# USB.net
KiCad netlist of a schematic drawn in Altium Designer
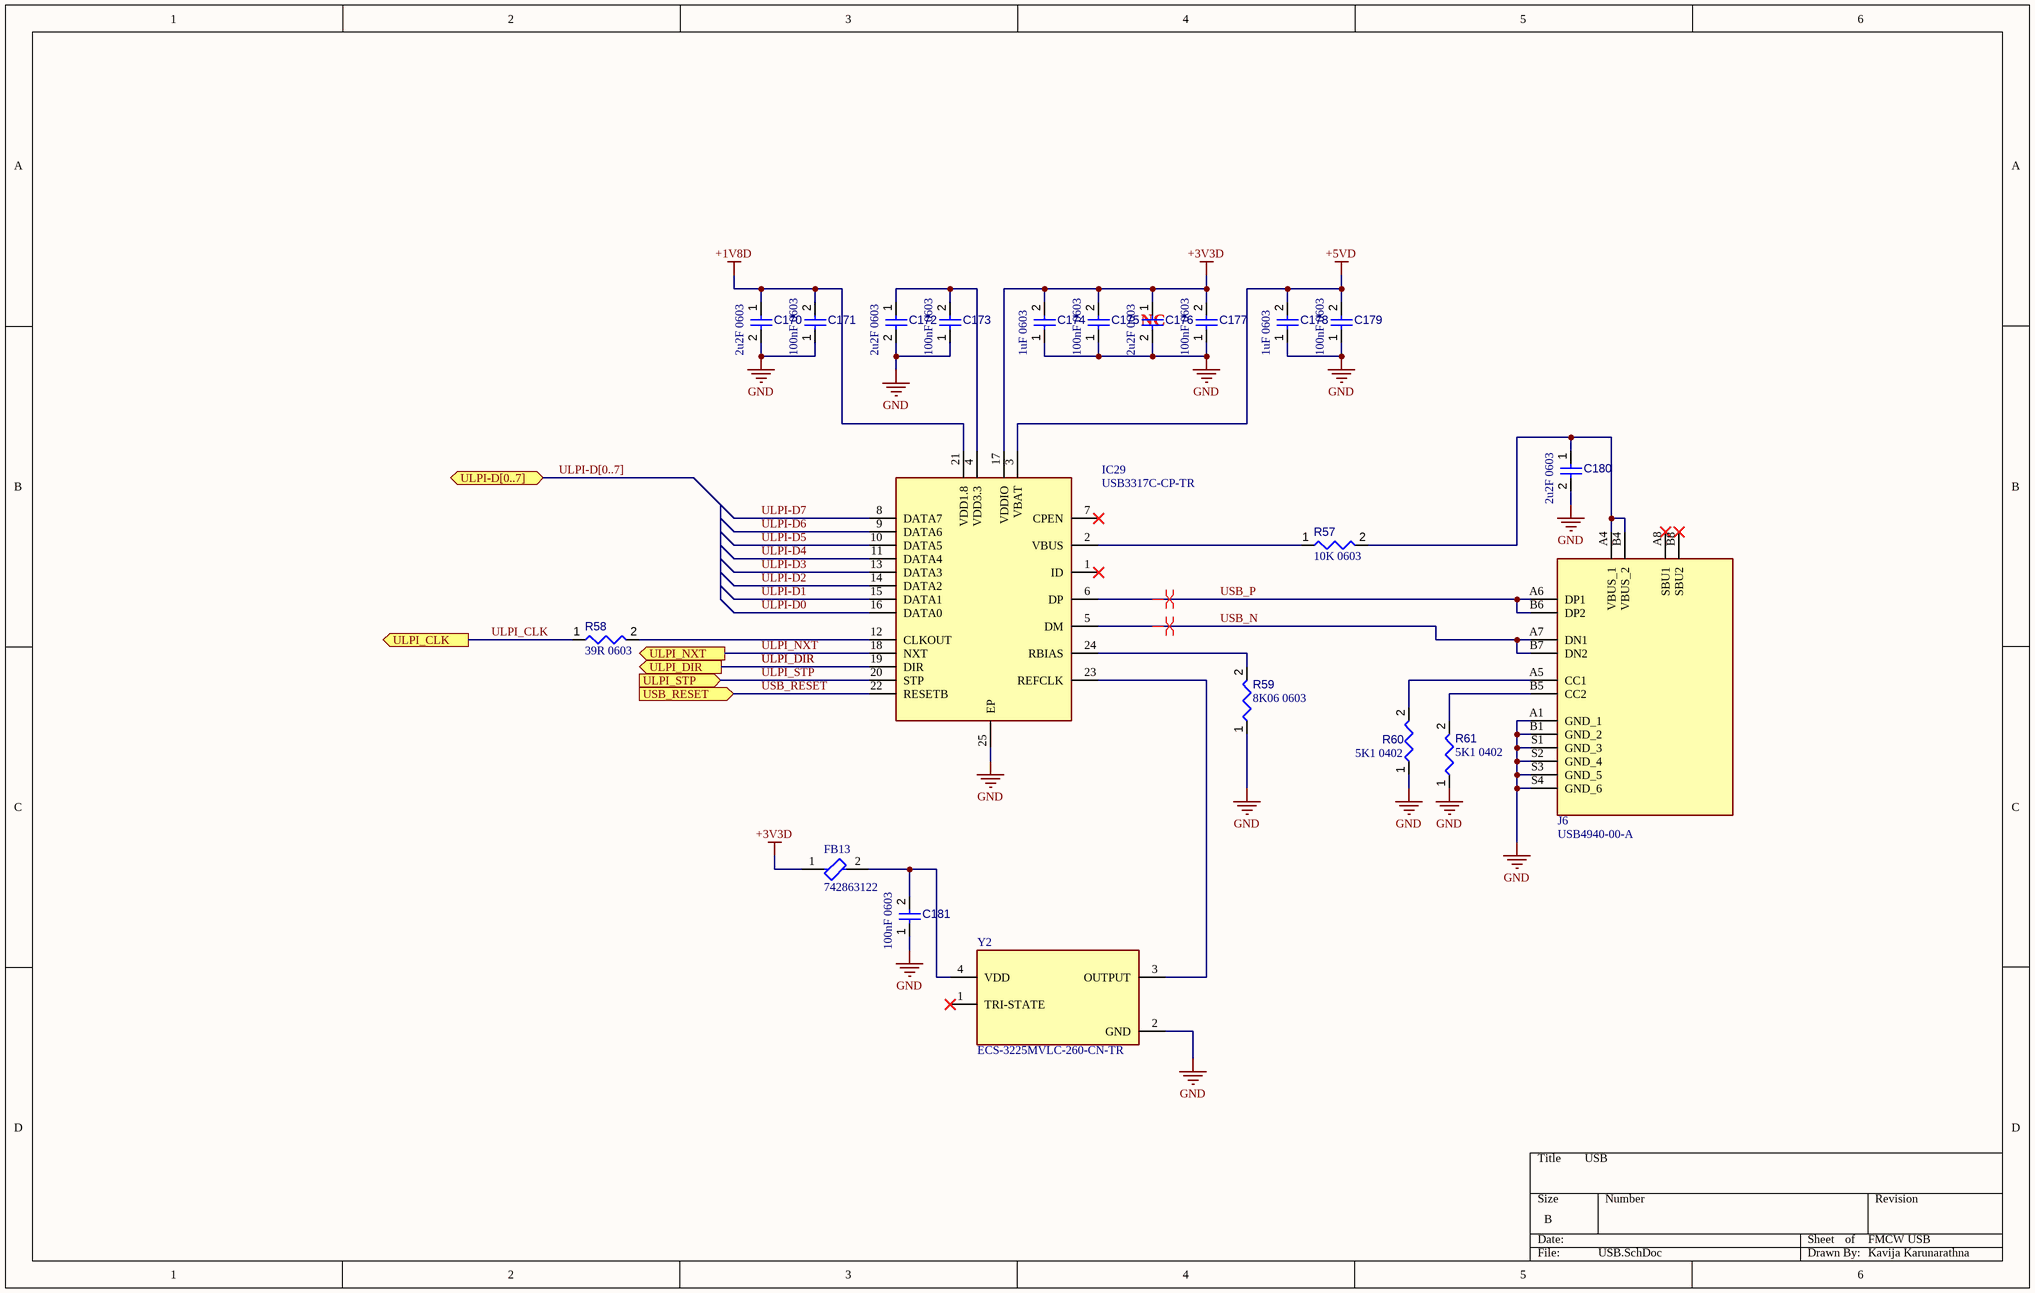
[diagram p0: USB.SchDoc]

(export (version "E")
  (design (tool "Eeschema 10.0.6"))
  (components
    (comp (ref "C170")
      (value "2u2F 0603")
      (footprint "CAPC0603(1608)100_L")
      (description "Multilayer Ceramic Capacitors MLCC - SMD/SMT 0603 10nF 16volts X7R 10%")
      (fields (field (name "TOLERANCE") "20%") (field (name "MANUFACTURER PART NO") "VJ0603G225KXQCW1BC"))
      (libsource (lib "Kavija Karunarathna") (part "CAP-NP-2"))
    )
    (comp (ref "C171")
      (value "100nF 0603")
      (footprint "CAPC0603(1608)100_L")
      (description "Chip Capacitor, 1µF +/-0.1%, 25V, 0603, Thickness 1 mm")
      (fields (field (name "TOLERANCE") "20%") (field (name "MANUFACTURER PART NO") "0603X104K250CT"))
      (libsource (lib "Kavija Karunarathna") (part "CAP-NP-2"))
    )
    (comp (ref "C172")
      (value "2u2F 0603")
      (footprint "CAPC0603(1608)100_L")
      (description "Multilayer Ceramic Capacitors MLCC - SMD/SMT 0603 10nF 16volts X7R 10%")
      (fields (field (name "TOLERANCE") "20%") (field (name "MANUFACTURER PART NO") "VJ0603G225KXQCW1BC"))
      (libsource (lib "Kavija Karunarathna") (part "CAP-NP-2"))
    )
    (comp (ref "C173")
      (value "100nF 0603")
      (footprint "CAPC0603(1608)100_L")
      (description "Chip Capacitor, 1µF +/-0.1%, 25V, 0603, Thickness 1 mm")
      (fields (field (name "TOLERANCE") "20%") (field (name "MANUFACTURER PART NO") "0603X104K250CT"))
      (libsource (lib "Kavija Karunarathna") (part "CAP-NP-2"))
    )
    (comp (ref "C174")
      (value "1uF 0603")
      (footprint "CAPC0603(1608)100_L")
      (description "Chip Capacitor, 1µF +/-0.1%, 25V, 0603, Thickness 1 mm")
      (fields (field (name "TOLERANCE") "20%") (field (name "MANUFACTURER PART NO") "0603YC105KAZ2A"))
      (libsource (lib "Kavija Karunarathna") (part "CAP-NP-2"))
    )
    (comp (ref "C175")
      (value "100nF 0603")
      (footprint "CAPC0603(1608)100_L")
      (description "Chip Capacitor, 1µF +/-0.1%, 25V, 0603, Thickness 1 mm")
      (fields (field (name "TOLERANCE") "20%") (field (name "MANUFACTURER PART NO") "0603X104K250CT"))
      (libsource (lib "Kavija Karunarathna") (part "CAP-NP-2"))
    )
    (comp (ref "C176")
      (value "2u2F 0603")
      (footprint "CAPC0603(1608)100_L")
      (description "Multilayer Ceramic Capacitors MLCC - SMD/SMT 0603 10nF 16volts X7R 10%")
      (fields (field (name "TOLERANCE") "20%") (field (name "MANUFACTURER PART NO") "VJ0603G225KXQCW1BC"))
      (libsource (lib "Kavija Karunarathna") (part "CAP-NP-2"))
    )
    (comp (ref "C177")
      (value "100nF 0603")
      (footprint "CAPC0603(1608)100_L")
      (description "Chip Capacitor, 1µF +/-0.1%, 25V, 0603, Thickness 1 mm")
      (fields (field (name "TOLERANCE") "20%") (field (name "MANUFACTURER PART NO") "0603X104K250CT"))
      (libsource (lib "Kavija Karunarathna") (part "CAP-NP-2"))
    )
    (comp (ref "C178")
      (value "1uF 0603")
      (footprint "CAPC0603(1608)100_L")
      (description "Chip Capacitor, 1µF +/-0.1%, 25V, 0603, Thickness 1 mm")
      (fields (field (name "TOLERANCE") "20%") (field (name "MANUFACTURER PART NO") "0603YC105KAZ2A"))
      (libsource (lib "Kavija Karunarathna") (part "CAP-NP-2"))
    )
    (comp (ref "C179")
      (value "100nF 0603")
      (footprint "CAPC0603(1608)100_L")
      (description "Chip Capacitor, 1µF +/-0.1%, 25V, 0603, Thickness 1 mm")
      (fields (field (name "TOLERANCE") "20%") (field (name "MANUFACTURER PART NO") "0603X104K250CT"))
      (libsource (lib "Kavija Karunarathna") (part "CAP-NP-2"))
    )
    (comp (ref "C180")
      (value "2u2F 0603")
      (footprint "CAPC0603(1608)100_L")
      (description "Multilayer Ceramic Capacitors MLCC - SMD/SMT 0603 10nF 16volts X7R 10%")
      (fields (field (name "TOLERANCE") "20%") (field (name "MANUFACTURER PART NO") "VJ0603G225KXQCW1BC"))
      (libsource (lib "Kavija Karunarathna") (part "CAP-NP-2"))
    )
    (comp (ref "C181")
      (value "100nF 0603")
      (footprint "CAPC0603(1608)100_L")
      (description "Chip Capacitor, 1µF +/-0.1%, 25V, 0603, Thickness 1 mm")
      (fields (field (name "TOLERANCE") "20%") (field (name "MANUFACTURER PART NO") "0603X104K250CT"))
      (libsource (lib "Kavija Karunarathna") (part "CAP-NP-2"))
    )
    (comp (ref "FB13")
      (value "742863122")
      (footprint "FB-0603")
      (description "FERRITE BEAD 0603")
      (fields (field (name "MOUSER PART NO") "710-742863122"))
      (libsource (lib "SchLib") (part "742792662-FB"))
    )
    (comp (ref "IC29")
      (value "USB3317C-CP-TR")
      (footprint "QFN50P400X400X100-25N-D")
      (description "Integrated Circuit")
      (fields (field (name "MOUSER PART NO") "886-USB3317C-CP-TR"))
      (libsource (lib "SchLib") (part "USB3317C-CP-TR"))
    )
    (comp (ref "J6")
      (value "USB4940-00-A")
      (footprint "USB494000A")
      (description "USB Connectors USB Type C, 2.0, 16P, Receptacle, Horizontal, Top Mount, SMT,T&R")
      (fields (field (name "MOUSER PART NO") "640-USB4940-00-A"))
      (libsource (lib "SchLib") (part "USB4940-00-A"))
    )
    (comp (ref "R57")
      (value "10K 0603")
      (footprint "RESC0603(1608)_L")
      (description "Thin Film Resistors - SMD CHIP RESISTOR Precision")
      (fields (field (name "POWER") "100mW") (field (name "TOLERANCE") "5%"))
      (libsource (lib "Kavija Karunarathna") (part "120R3J"))
    )
    (comp (ref "R58")
      (value "39R 0603")
      (footprint "RESC0603(1608)_L")
      (description "Thick Film Resistors - SMD 1/10Watt 39ohms 1% Commercial Use")
      (fields (field (name "POWER") "100mW") (field (name "TOLERANCE") "5%"))
      (libsource (lib "Kavija Karunarathna") (part "120R3J"))
    )
    (comp (ref "R59")
      (value "8K06 0603")
      (footprint "RESC0603(1608)_L")
      (description "Thin Film Resistors - SMD RN 0603 8K06 0.1% 10PPM")
      (fields (field (name "POWER") "100mW") (field (name "TOLERANCE") "5%"))
      (libsource (lib "Kavija Karunarathna") (part "120R3J"))
    )
    (comp (ref "R60")
      (value "5K1 0402")
      (footprint "RESC0402(1005)_L")
      (description "Thick Film Resistors - SMD 1/10 Watt 5.1Kohms 1%")
      (fields (field (name "TOLERANCE") "1%") (field (name "POWER") "100mW"))
      (libsource (lib "Kavija Karunarathna") (part "383KR2F"))
    )
    (comp (ref "R61")
      (value "5K1 0402")
      (footprint "RESC0402(1005)_L")
      (description "Thick Film Resistors - SMD 1/10 Watt 5.1Kohms 1%")
      (fields (field (name "TOLERANCE") "1%") (field (name "POWER") "100mW"))
      (libsource (lib "Kavija Karunarathna") (part "383KR2F"))
    )
    (comp (ref "Y2")
      (value "ECS-3225MVLC-260-CN-TR")
      (footprint "OSC_ECS-3225MVLC-260-CN-TR")
      (description "26 MHz XO (Standard) CMOS Oscillator 1.8V ~ 3.3V Enable/Disable 4-SMD, No Lead")
      (fields (field (name "MF") "ECS Inc."))
      (libsource (lib "Kavija Karunarathna") (part "ECS-3225MVLC-260-CN-TR"))
    )
  )
  (nets
    (net (code "1") (name "+1V8D") (class "Default")
      (node (ref "C170") (pin "1") (pinfunction "1_1") (pintype "passive"))
      (node (ref "C171") (pin "2") (pinfunction "2_2") (pintype "passive"))
      (node (ref "IC29") (pin "21") (pinfunction "VDD1.8_21") (pintype "passive"))
    )
    (net (code "2") (name "+3V3D") (class "Default")
      (node (ref "C174") (pin "2") (pinfunction "2_2") (pintype "passive"))
      (node (ref "C175") (pin "2") (pinfunction "2_2") (pintype "passive"))
      (node (ref "C176") (pin "1") (pinfunction "1_1") (pintype "passive"))
      (node (ref "C177") (pin "2") (pinfunction "2_2") (pintype "passive"))
      (node (ref "FB13") (pin "1") (pinfunction "1_1") (pintype "passive"))
      (node (ref "IC29") (pin "17") (pinfunction "VDDIO_17") (pintype "passive"))
    )
    (net (code "3") (name "+5VD") (class "Default")
      (node (ref "C178") (pin "2") (pinfunction "2_2") (pintype "passive"))
      (node (ref "C179") (pin "2") (pinfunction "2_2") (pintype "passive"))
      (node (ref "IC29") (pin "3") (pinfunction "VBAT_3") (pintype "passive"))
    )
    (net (code "4") (name "/ULPI-D0") (class "Default")
      (node (ref "IC29") (pin "16") (pinfunction "DATA0_16") (pintype "passive"))
    )
    (net (code "5") (name "/ULPI-D1") (class "Default")
      (node (ref "IC29") (pin "15") (pinfunction "DATA1_15") (pintype "passive"))
    )
    (net (code "6") (name "/ULPI-D2") (class "Default")
      (node (ref "IC29") (pin "14") (pinfunction "DATA2_14") (pintype "passive"))
    )
    (net (code "7") (name "/ULPI-D3") (class "Default")
      (node (ref "IC29") (pin "13") (pinfunction "DATA3_13") (pintype "passive"))
    )
    (net (code "8") (name "/ULPI-D4") (class "Default")
      (node (ref "IC29") (pin "11") (pinfunction "DATA4_11") (pintype "passive"))
    )
    (net (code "9") (name "/ULPI-D5") (class "Default")
      (node (ref "IC29") (pin "10") (pinfunction "DATA5_10") (pintype "passive"))
    )
    (net (code "10") (name "/ULPI-D6") (class "Default")
      (node (ref "IC29") (pin "9") (pinfunction "DATA6_9") (pintype "passive"))
    )
    (net (code "11") (name "/ULPI-D7") (class "Default")
      (node (ref "IC29") (pin "8") (pinfunction "DATA7_8") (pintype "passive"))
    )
    (net (code "13") (name "/ULPI_CLK") (class "Default")
      (node (ref "R58") (pin "1") (pinfunction "1_1") (pintype "passive"))
    )
    (net (code "14") (name "/ULPI_DIR") (class "Default")
      (node (ref "IC29") (pin "19") (pinfunction "DIR_19") (pintype "passive"))
    )
    (net (code "15") (name "/ULPI_NXT") (class "Default")
      (node (ref "IC29") (pin "18") (pinfunction "NXT_18") (pintype "passive"))
    )
    (net (code "16") (name "/ULPI_STP") (class "Default")
      (node (ref "IC29") (pin "20") (pinfunction "STP_20") (pintype "passive"))
    )
    (net (code "17") (name "/USB_N") (class "Default")
      (node (ref "IC29") (pin "5") (pinfunction "DM_5") (pintype "passive"))
      (node (ref "J6") (pin "A7") (pinfunction "DN1_A7") (pintype "passive"))
      (node (ref "J6") (pin "B7") (pinfunction "DN2_B7") (pintype "passive"))
    )
    (net (code "18") (name "/USB_P") (class "Default")
      (node (ref "IC29") (pin "6") (pinfunction "DP_6") (pintype "passive"))
      (node (ref "J6") (pin "A6") (pinfunction "DP1_A6") (pintype "passive"))
      (node (ref "J6") (pin "B6") (pinfunction "DP2_B6") (pintype "passive"))
    )
    (net (code "19") (name "/USB_RESET") (class "Default")
      (node (ref "IC29") (pin "22") (pinfunction "RESETB_22") (pintype "passive"))
    )
    (net (code "20") (name "GND") (class "Default")
      (node (ref "C170") (pin "2") (pinfunction "2_2") (pintype "passive"))
      (node (ref "C171") (pin "1") (pinfunction "1_1") (pintype "passive"))
      (node (ref "C172") (pin "2") (pinfunction "2_2") (pintype "passive"))
      (node (ref "C173") (pin "1") (pinfunction "1_1") (pintype "passive"))
      (node (ref "C174") (pin "1") (pinfunction "1_1") (pintype "passive"))
      (node (ref "C175") (pin "1") (pinfunction "1_1") (pintype "passive"))
      (node (ref "C176") (pin "2") (pinfunction "2_2") (pintype "passive"))
      (node (ref "C177") (pin "1") (pinfunction "1_1") (pintype "passive"))
      (node (ref "C178") (pin "1") (pinfunction "1_1") (pintype "passive"))
      (node (ref "C179") (pin "1") (pinfunction "1_1") (pintype "passive"))
      (node (ref "C180") (pin "2") (pinfunction "2_2") (pintype "passive"))
      (node (ref "C181") (pin "1") (pinfunction "1_1") (pintype "passive"))
      (node (ref "IC29") (pin "25") (pinfunction "EP_25") (pintype "passive"))
      (node (ref "J6") (pin "A1") (pinfunction "GND_1_A1") (pintype "passive"))
      (node (ref "J6") (pin "B1") (pinfunction "GND_2_B1") (pintype "passive"))
      (node (ref "J6") (pin "S1") (pinfunction "GND_3_S1") (pintype "passive"))
      (node (ref "J6") (pin "S2") (pinfunction "GND_4_S2") (pintype "passive"))
      (node (ref "J6") (pin "S3") (pinfunction "GND_5_S3") (pintype "passive"))
      (node (ref "J6") (pin "S4") (pinfunction "GND_6_S4") (pintype "passive"))
      (node (ref "R59") (pin "1") (pinfunction "1_1") (pintype "passive"))
      (node (ref "R60") (pin "1") (pinfunction "1_1") (pintype "passive"))
      (node (ref "R61") (pin "1") (pinfunction "1_1") (pintype "passive"))
      (node (ref "Y2") (pin "2") (pinfunction "GND_2") (pintype "power_in"))
    )
    (net (code "21") (name "Net-(IC29-CLKOUT)") (class "Default")
      (node (ref "IC29") (pin "12") (pinfunction "CLKOUT_12") (pintype "passive"))
      (node (ref "R58") (pin "2") (pinfunction "2_2") (pintype "passive"))
    )
    (net (code "22") (name "Net-(IC29-RBIAS)") (class "Default")
      (node (ref "IC29") (pin "24") (pinfunction "RBIAS_24") (pintype "passive"))
      (node (ref "R59") (pin "2") (pinfunction "2_2") (pintype "passive"))
    )
    (net (code "23") (name "Net-(IC29-REFCLK)") (class "Default")
      (node (ref "IC29") (pin "23") (pinfunction "REFCLK_23") (pintype "passive"))
      (node (ref "Y2") (pin "3") (pinfunction "OUTPUT_3") (pintype "passive"))
    )
    (net (code "24") (name "Net-(IC29-VBUS)") (class "Default")
      (node (ref "IC29") (pin "2") (pinfunction "VBUS_2") (pintype "passive"))
      (node (ref "R57") (pin "1") (pinfunction "1_1") (pintype "passive"))
    )
    (net (code "25") (name "Net-(IC29-VDD3.3)") (class "Default")
      (node (ref "C172") (pin "1") (pinfunction "1_1") (pintype "passive"))
      (node (ref "C173") (pin "2") (pinfunction "2_2") (pintype "passive"))
      (node (ref "IC29") (pin "4") (pinfunction "VDD3.3_4") (pintype "passive"))
    )
    (net (code "26") (name "Net-(J6-CC1)") (class "Default")
      (node (ref "J6") (pin "A5") (pinfunction "CC1_A5") (pintype "passive"))
      (node (ref "R60") (pin "2") (pinfunction "2_2") (pintype "passive"))
    )
    (net (code "27") (name "Net-(J6-CC2)") (class "Default")
      (node (ref "J6") (pin "B5") (pinfunction "CC2_B5") (pintype "passive"))
      (node (ref "R61") (pin "2") (pinfunction "2_2") (pintype "passive"))
    )
    (net (code "28") (name "Net-(J6-VBUS_1)") (class "Default")
      (node (ref "C180") (pin "1") (pinfunction "1_1") (pintype "passive"))
      (node (ref "J6") (pin "A4") (pinfunction "VBUS_1_A4") (pintype "passive"))
      (node (ref "J6") (pin "B4") (pinfunction "VBUS_2_B4") (pintype "passive"))
      (node (ref "R57") (pin "2") (pinfunction "2_2") (pintype "passive"))
    )
    (net (code "29") (name "Net-(Y2-VDD)") (class "Default")
      (node (ref "C181") (pin "2") (pinfunction "2_2") (pintype "passive"))
      (node (ref "FB13") (pin "2") (pinfunction "2_2") (pintype "passive"))
      (node (ref "Y2") (pin "4") (pinfunction "VDD_4") (pintype "passive"))
    )
    (net (code "30") (name "unconnected-(IC29-CPEN-Pad7)") (class "Default")
      (node (ref "IC29") (pin "7") (pinfunction "CPEN_7") (pintype "passive+no_connect"))
    )
    (net (code "31") (name "unconnected-(IC29-ID-Pad1)") (class "Default")
      (node (ref "IC29") (pin "1") (pinfunction "ID_1") (pintype "passive+no_connect"))
    )
    (net (code "32") (name "unconnected-(J6-SBU1-PadA8)") (class "Default")
      (node (ref "J6") (pin "A8") (pinfunction "SBU1_A8") (pintype "passive+no_connect"))
    )
    (net (code "33") (name "unconnected-(J6-SBU2-PadB8)") (class "Default")
      (node (ref "J6") (pin "B8") (pinfunction "SBU2_B8") (pintype "passive+no_connect"))
    )
    (net (code "34") (name "unconnected-(Y2-TRI-STATE-Pad1)") (class "Default")
      (node (ref "Y2") (pin "1") (pinfunction "TRI-STATE_1") (pintype "passive+no_connect"))
    )
  )
)
